# ESP32_Interface.net
KiCad netlist of a schematic drawn in Altium Designer
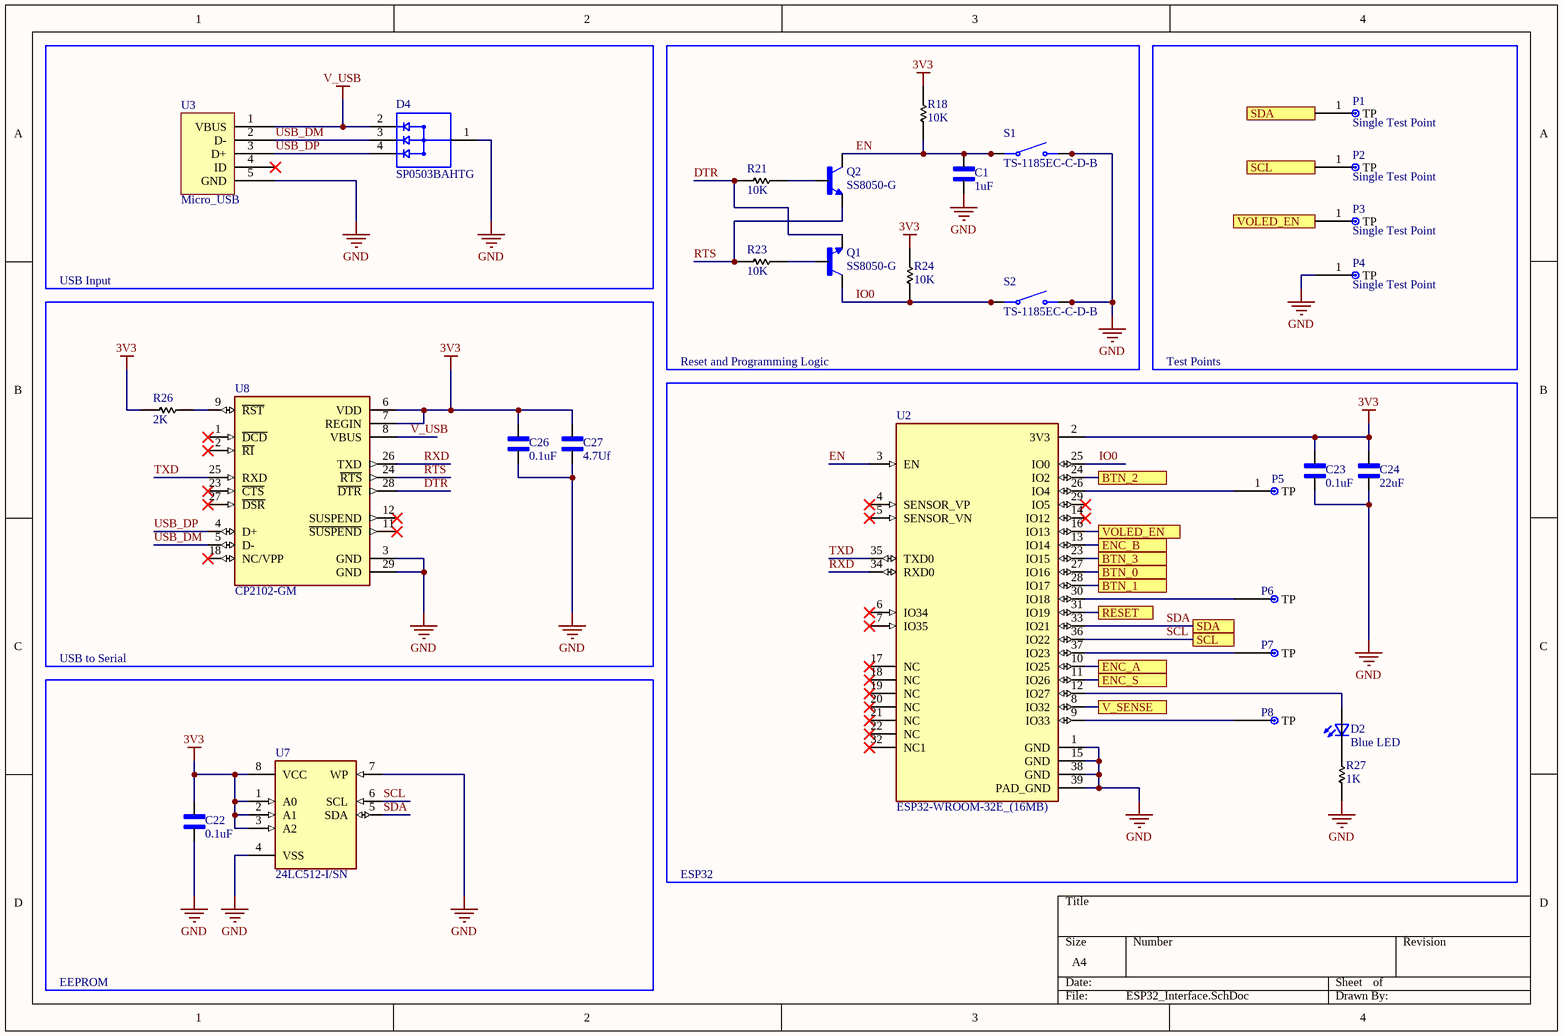
[diagram p0: ESP32_Interface.SchDoc]

(export (version "E")
  (design (tool "Eeschema 10.0.6"))
  (components
    (comp (ref "C1")
      (value "1uF")
      (footprint "CHIP_0603")
      (description "Generic 0603 Ceramic Capacitor")
      (fields (field (name "MP") "AC0402FR-071ML") (field (name "MF") "Yageo"))
      (libsource (lib "Guitar_Multi_Effect_lib") (part "0603 Ceramic Capacitor"))
    )
    (comp (ref "C22")
      (value "0.1uF")
      (footprint "CHIP_0603")
      (description "Generic 0603 Ceramic Capacitor")
      (fields (field (name "MP") "AC0402FR-071ML") (field (name "MF") "Yageo"))
      (libsource (lib "Guitar_Multi_Effect_lib") (part "0603 Ceramic Capacitor"))
    )
    (comp (ref "C23")
      (value "0.1uF")
      (footprint "CHIP_0603")
      (description "Generic 0603 Ceramic Capacitor")
      (fields (field (name "MP") "AC0402FR-071ML") (field (name "MF") "Yageo"))
      (libsource (lib "Guitar_Multi_Effect_lib") (part "0603 Ceramic Capacitor"))
    )
    (comp (ref "C24")
      (value "22uF")
      (footprint "CHIP_0603")
      (description "Generic 0603 Ceramic Capacitor")
      (fields (field (name "MP") "AC0402FR-071ML") (field (name "MF") "Yageo"))
      (libsource (lib "Guitar_Multi_Effect_lib") (part "0603 Ceramic Capacitor"))
    )
    (comp (ref "C26")
      (value "0.1uF")
      (footprint "CHIP_0603")
      (description "Generic 0603 Ceramic Capacitor")
      (fields (field (name "MP") "AC0402FR-071ML") (field (name "MF") "Yageo"))
      (libsource (lib "Guitar_Multi_Effect_lib") (part "0603 Ceramic Capacitor"))
    )
    (comp (ref "C27")
      (value "4.7Uf")
      (footprint "CHIP_0603")
      (description "Generic 0603 Ceramic Capacitor")
      (fields (field (name "MP") "AC0402FR-071ML") (field (name "MF") "Yageo"))
      (libsource (lib "Guitar_Multi_Effect_lib") (part "0603 Ceramic Capacitor"))
    )
    (comp (ref "D2")
      (value "Blue LED")
      (footprint "0603 LED Generic")
      (description "0603 Generic LED")
      (libsource (lib "Guitar_Multi_Effect_lib") (part "0603 Generic LED"))
    )
    (comp (ref "D4")
      (value "SP0503BAHTG")
      (footprint "Multi_Effect_Interface_lib:SP0503BAHTG")
      (description "8.5V Clamp Ipp Tvs Diode Surface Mount SOT-143-4")
      (fields (field (name "MF") "Littelfuse Inc.") (field (name "DIGI-KEY_PART_NUMBER") "F2715CT-ND"))
      (libsource (lib "Guitar_Multi_Effect_Interface_lib") (part "SP0503BAHTG"))
    )
    (comp (ref "P1")
      (value "Single Test Point")
      (footprint "1 Solder Pad")
      (libsource (lib "Guitar_Multi_Effect_Interface_lib") (part "Single Test Point"))
    )
    (comp (ref "P2")
      (value "Single Test Point")
      (footprint "1 Solder Pad")
      (libsource (lib "Guitar_Multi_Effect_Interface_lib") (part "Single Test Point"))
    )
    (comp (ref "P3")
      (value "Single Test Point")
      (footprint "1 Solder Pad")
      (libsource (lib "Guitar_Multi_Effect_Interface_lib") (part "Single Test Point"))
    )
    (comp (ref "P4")
      (value "Single Test Point")
      (footprint "1 Solder Pad")
      (libsource (lib "Guitar_Multi_Effect_Interface_lib") (part "Single Test Point"))
    )
    (comp (ref "P5")
      (value "Single Test Point")
      (footprint "1 Solder Pad")
      (libsource (lib "Guitar_Multi_Effect_Interface_lib") (part "Single Test Point"))
    )
    (comp (ref "P6")
      (value "Single Test Point")
      (footprint "1 Solder Pad")
      (libsource (lib "") (part "Single Test Point_1"))
    )
    (comp (ref "P7")
      (value "Single Test Point")
      (footprint "1 Solder Pad")
      (libsource (lib "") (part "Single Test Point_1"))
    )
    (comp (ref "P8")
      (value "Single Test Point")
      (footprint "1 Solder Pad")
      (libsource (lib "") (part "Single Test Point_1"))
    )
    (comp (ref "Q1")
      (value "SS8050-G")
      (footprint "SS8050-G")
      (description "NPN TRANSISTOR 1.5A 40V SOT-23 R")
      (libsource (lib "Guitar_Multi_Effect_lib") (part "SS8050-G"))
    )
    (comp (ref "Q2")
      (value "SS8050-G")
      (footprint "SS8050-G")
      (description "NPN TRANSISTOR 1.5A 40V SOT-23 R")
      (libsource (lib "") (part "SS8050-G_1"))
    )
    (comp (ref "R18")
      (value "10K")
      (footprint "CHIP_R_0603")
      (description "Generic 0603 Resistor")
      (libsource (lib "Guitar_Multi_Effect_lib") (part "0603 Generic Resistor"))
    )
    (comp (ref "R21")
      (value "10K")
      (footprint "CHIP_R_0603")
      (description "Generic 0603 Resistor")
      (libsource (lib "Guitar_Multi_Effect_lib") (part "0603 Generic Resistor"))
    )
    (comp (ref "R23")
      (value "10K")
      (footprint "CHIP_R_0603")
      (description "Generic 0603 Resistor")
      (libsource (lib "Guitar_Multi_Effect_lib") (part "0603 Generic Resistor"))
    )
    (comp (ref "R24")
      (value "10K")
      (footprint "CHIP_R_0603")
      (description "Generic 0603 Resistor")
      (libsource (lib "Guitar_Multi_Effect_lib") (part "0603 Generic Resistor"))
    )
    (comp (ref "R26")
      (value "2K")
      (footprint "CHIP_R_0603")
      (description "Generic 0603 Resistor")
      (libsource (lib "Guitar_Multi_Effect_lib") (part "0603 Generic Resistor"))
    )
    (comp (ref "R27")
      (value "1K")
      (footprint "CHIP_R_0603")
      (description "Generic 0603 Resistor")
      (libsource (lib "Guitar_Multi_Effect_lib") (part "0603 Generic Resistor"))
    )
    (comp (ref "S1")
      (value "TS-1185EC-C-D-B")
      (footprint "TS-1185EC-C-D-B")
      (description "SMD Tactile Switche - 3mm 2mm 50mA 3.65mm SPST 12V")
      (libsource (lib "Guitar_Multi_Effect_lib") (part "TS-1185EC-C-D-B"))
    )
    (comp (ref "S2")
      (value "TS-1185EC-C-D-B")
      (footprint "TS-1185EC-C-D-B")
      (description "SMD Tactile Switche - 3mm 2mm 50mA 3.65mm SPST 12V")
      (libsource (lib "Guitar_Multi_Effect_lib") (part "TS-1185EC-C-D-B"))
    )
    (comp (ref "U2")
      (value "ESP32-WROOM-32E_(16MB)")
      (footprint "MODULE_ESP32-WROOM-32E")
      (fields (field (name "MP") "ESP32-WROOM-32E (16MB)") (field (name "MF") "Espressif Systems"))
      (libsource (lib "Guitar_Multi_Effect_lib") (part "ESP32-WROOM-32E_(16MB)"))
    )
    (comp (ref "U3")
      (value "Micro_USB")
      (footprint "U254-051T-4BH83-F1S")
      (description "XKB Connectivity U254-051T-4BH83-F1S")
      (libsource (lib "Guitar_Multi_Effect_lib") (part "Micro_USB"))
    )
    (comp (ref "U7")
      (value "24LC512-I/SN")
      (footprint "24LC512-I/SN")
      (description "512K I2C Serial EEPROM")
      (libsource (lib "Guitar_Multi_Effect_lib") (part "24LC512-I/SN"))
    )
    (comp (ref "U8")
      (value "CP2102-GM")
      (footprint "QFN50P500X500X100-29N")
      (description "USB Bridge, USB to UART USB 2.0 UART Interface 28-QFN _5x5_")
      (fields (field (name "MF") "Silicon Labs"))
      (libsource (lib "Guitar_Multi_Effect_lib") (part "CP2102-GM"))
    )
  )
  (nets
    (net (code "1") (name "/BTN_0") (class "Default")
      (node (ref "U2") (pin "27") (pinfunction "IO16_27") (pintype "bidirectional"))
    )
    (net (code "2") (name "/BTN_1") (class "Default")
      (node (ref "U2") (pin "28") (pinfunction "IO17_28") (pintype "bidirectional"))
    )
    (net (code "3") (name "/BTN_2") (class "Default")
      (node (ref "U2") (pin "24") (pinfunction "IO2_24") (pintype "bidirectional"))
    )
    (net (code "4") (name "/BTN_3") (class "Default")
      (node (ref "U2") (pin "23") (pinfunction "IO15_23") (pintype "bidirectional"))
    )
    (net (code "5") (name "/DTR") (class "Default")
      (node (ref "Q1") (pin "2") (pinfunction "E_2") (pintype "passive"))
      (node (ref "R21") (pin "2") (pinfunction "2_2") (pintype "passive"))
      (node (ref "U8") (pin "28") (pinfunction "~{DTR}_28") (pintype "output"))
    )
    (net (code "6") (name "/EN") (class "Default")
      (node (ref "C1") (pin "1") (pinfunction "1_1") (pintype "passive"))
      (node (ref "Q2") (pin "3") (pinfunction "C_3") (pintype "passive"))
      (node (ref "R18") (pin "2") (pinfunction "2_2") (pintype "passive"))
      (node (ref "S1") (pin "1") (pinfunction "COM_1") (pintype "passive"))
      (node (ref "S1") (pin "2") (pinfunction "COM_2") (pintype "passive"))
      (node (ref "U2") (pin "3") (pinfunction "EN_3") (pintype "input"))
    )
    (net (code "7") (name "/ENC_A") (class "Default")
      (node (ref "U2") (pin "10") (pinfunction "IO25_10") (pintype "bidirectional"))
    )
    (net (code "8") (name "/ENC_B") (class "Default")
      (node (ref "U2") (pin "13") (pinfunction "IO14_13") (pintype "bidirectional"))
    )
    (net (code "9") (name "/ENC_S") (class "Default")
      (node (ref "U2") (pin "11") (pinfunction "IO26_11") (pintype "bidirectional"))
    )
    (net (code "10") (name "/IO0") (class "Default")
      (node (ref "Q1") (pin "3") (pinfunction "C_3") (pintype "passive"))
      (node (ref "R24") (pin "2") (pinfunction "2_2") (pintype "passive"))
      (node (ref "S2") (pin "1") (pinfunction "COM_1") (pintype "passive"))
      (node (ref "S2") (pin "2") (pinfunction "COM_2") (pintype "passive"))
      (node (ref "U2") (pin "25") (pinfunction "IO0_25") (pintype "bidirectional"))
    )
    (net (code "11") (name "/RESET") (class "Default")
      (node (ref "U2") (pin "31") (pinfunction "IO19_31") (pintype "bidirectional"))
    )
    (net (code "12") (name "/RTS") (class "Default")
      (node (ref "Q2") (pin "2") (pinfunction "E_2") (pintype "passive"))
      (node (ref "R23") (pin "2") (pinfunction "2_2") (pintype "passive"))
      (node (ref "U8") (pin "24") (pinfunction "~{RTS}_24") (pintype "output"))
    )
    (net (code "13") (name "/RXD") (class "Default")
      (node (ref "U2") (pin "34") (pinfunction "RXD0_34") (pintype "bidirectional"))
      (node (ref "U8") (pin "26") (pinfunction "TXD_26") (pintype "output"))
    )
    (net (code "14") (name "/SCL") (class "Default")
      (node (ref "P2") (pin "1") (pinfunction "TP_1") (pintype "passive"))
      (node (ref "U2") (pin "36") (pinfunction "IO22_36") (pintype "bidirectional"))
      (node (ref "U7") (pin "6") (pinfunction "SCL_6") (pintype "input"))
    )
    (net (code "15") (name "/SDA") (class "Default")
      (node (ref "P1") (pin "1") (pinfunction "TP_1") (pintype "passive"))
      (node (ref "U2") (pin "33") (pinfunction "IO21_33") (pintype "bidirectional"))
      (node (ref "U7") (pin "5") (pinfunction "SDA_5") (pintype "bidirectional"))
    )
    (net (code "16") (name "/TXD") (class "Default")
      (node (ref "U2") (pin "35") (pinfunction "TXD0_35") (pintype "bidirectional"))
      (node (ref "U8") (pin "25") (pinfunction "RXD_25") (pintype "input"))
    )
    (net (code "17") (name "/USB_DM") (class "Default")
      (node (ref "D4") (pin "3") (pinfunction "3_3") (pintype "passive"))
      (node (ref "U3") (pin "2") (pinfunction "D-_2") (pintype "passive"))
      (node (ref "U8") (pin "5") (pinfunction "D-_5") (pintype "bidirectional"))
    )
    (net (code "18") (name "/USB_DP") (class "Default")
      (node (ref "D4") (pin "4") (pinfunction "4_4") (pintype "passive"))
      (node (ref "U3") (pin "3") (pinfunction "D+_3") (pintype "passive"))
      (node (ref "U8") (pin "4") (pinfunction "D+_4") (pintype "bidirectional"))
    )
    (net (code "19") (name "/VOLED_EN") (class "Default")
      (node (ref "P3") (pin "1") (pinfunction "TP_1") (pintype "passive"))
      (node (ref "U2") (pin "16") (pinfunction "IO13_16") (pintype "bidirectional"))
    )
    (net (code "20") (name "/V_SENSE") (class "Default")
      (node (ref "U2") (pin "8") (pinfunction "IO32_8") (pintype "bidirectional"))
    )
    (net (code "21") (name "3V3") (class "Default")
      (node (ref "C22") (pin "1") (pinfunction "1_1") (pintype "passive"))
      (node (ref "C23") (pin "1") (pinfunction "1_1") (pintype "passive"))
      (node (ref "C24") (pin "1") (pinfunction "1_1") (pintype "passive"))
      (node (ref "C26") (pin "1") (pinfunction "1_1") (pintype "passive"))
      (node (ref "C27") (pin "1") (pinfunction "1_1") (pintype "passive"))
      (node (ref "R18") (pin "1") (pinfunction "1_1") (pintype "passive"))
      (node (ref "R24") (pin "1") (pinfunction "1_1") (pintype "passive"))
      (node (ref "R26") (pin "2") (pinfunction "2_2") (pintype "passive"))
      (node (ref "U2") (pin "2") (pinfunction "3V3_2") (pintype "power_in"))
      (node (ref "U7") (pin "1") (pinfunction "A0_1") (pintype "input"))
      (node (ref "U7") (pin "2") (pinfunction "A1_2") (pintype "input"))
      (node (ref "U7") (pin "3") (pinfunction "A2_3") (pintype "input"))
      (node (ref "U7") (pin "8") (pinfunction "VCC_8") (pintype "power_in"))
      (node (ref "U8") (pin "6") (pinfunction "VDD_6") (pintype "power_in"))
      (node (ref "U8") (pin "7") (pinfunction "REGIN_7") (pintype "power_in"))
    )
    (net (code "22") (name "GND") (class "Default")
      (node (ref "C1") (pin "2") (pinfunction "2_2") (pintype "passive"))
      (node (ref "C22") (pin "2") (pinfunction "2_2") (pintype "passive"))
      (node (ref "C23") (pin "2") (pinfunction "2_2") (pintype "passive"))
      (node (ref "C24") (pin "2") (pinfunction "2_2") (pintype "passive"))
      (node (ref "C26") (pin "2") (pinfunction "2_2") (pintype "passive"))
      (node (ref "C27") (pin "2") (pinfunction "2_2") (pintype "passive"))
      (node (ref "D4") (pin "1") (pinfunction "1_1") (pintype "passive"))
      (node (ref "P4") (pin "1") (pinfunction "TP_1") (pintype "passive"))
      (node (ref "R27") (pin "2") (pinfunction "2_2") (pintype "passive"))
      (node (ref "S1") (pin "3") (pinfunction "NO_3") (pintype "passive"))
      (node (ref "S1") (pin "4") (pinfunction "NO_4") (pintype "passive"))
      (node (ref "S2") (pin "3") (pinfunction "NO_3") (pintype "passive"))
      (node (ref "S2") (pin "4") (pinfunction "NO_4") (pintype "passive"))
      (node (ref "U2") (pin "1") (pinfunction "GND_1") (pintype "power_in"))
      (node (ref "U2") (pin "15") (pinfunction "GND_15") (pintype "power_in"))
      (node (ref "U2") (pin "38") (pinfunction "GND_38") (pintype "power_in"))
      (node (ref "U2") (pin "39") (pinfunction "PAD_GND_39") (pintype "power_in"))
      (node (ref "U3") (pin "5") (pinfunction "GND_5") (pintype "passive"))
      (node (ref "U7") (pin "4") (pinfunction "VSS_4") (pintype "passive"))
      (node (ref "U7") (pin "7") (pinfunction "WP_7") (pintype "input"))
      (node (ref "U8") (pin "29") (pinfunction "GND_29") (pintype "power_in"))
      (node (ref "U8") (pin "3") (pinfunction "GND_3") (pintype "power_in"))
    )
    (net (code "23") (name "Net-(D2-A2)") (class "Default")
      (node (ref "D2") (pin "2") (pinfunction "A2_2") (pintype "passive"))
      (node (ref "U2") (pin "12") (pinfunction "IO27_12") (pintype "bidirectional"))
    )
    (net (code "24") (name "Net-(D2-K2)") (class "Default")
      (node (ref "D2") (pin "1") (pinfunction "K2_1") (pintype "passive"))
      (node (ref "R27") (pin "1") (pinfunction "1_1") (pintype "passive"))
    )
    (net (code "25") (name "Net-(P5-TP)") (class "Default")
      (node (ref "P5") (pin "1") (pinfunction "TP_1") (pintype "passive"))
      (node (ref "U2") (pin "26") (pinfunction "IO4_26") (pintype "bidirectional"))
    )
    (net (code "26") (name "Net-(P6-TP)") (class "Default")
      (node (ref "P6") (pin "1") (pinfunction "TP_1") (pintype "passive"))
      (node (ref "U2") (pin "30") (pinfunction "IO18_30") (pintype "bidirectional"))
    )
    (net (code "27") (name "Net-(P7-TP)") (class "Default")
      (node (ref "P7") (pin "1") (pinfunction "TP_1") (pintype "passive"))
      (node (ref "U2") (pin "37") (pinfunction "IO23_37") (pintype "bidirectional"))
    )
    (net (code "28") (name "Net-(P8-TP)") (class "Default")
      (node (ref "P8") (pin "1") (pinfunction "TP_1") (pintype "passive"))
      (node (ref "U2") (pin "9") (pinfunction "IO33_9") (pintype "bidirectional"))
    )
    (net (code "29") (name "Net-(Q1-B)") (class "Default")
      (node (ref "Q1") (pin "1") (pinfunction "B_1") (pintype "passive"))
      (node (ref "R23") (pin "1") (pinfunction "1_1") (pintype "passive"))
    )
    (net (code "30") (name "Net-(Q2-B)") (class "Default")
      (node (ref "Q2") (pin "1") (pinfunction "B_1") (pintype "passive"))
      (node (ref "R21") (pin "1") (pinfunction "1_1") (pintype "passive"))
    )
    (net (code "31") (name "Net-(U8-~{RST})") (class "Default")
      (node (ref "R26") (pin "1") (pinfunction "1_1") (pintype "passive"))
      (node (ref "U8") (pin "9") (pinfunction "~{RST}_9") (pintype "bidirectional"))
    )
    (net (code "32") (name "V_USB") (class "Default")
      (node (ref "D4") (pin "2") (pinfunction "2_2") (pintype "passive"))
      (node (ref "U3") (pin "1") (pinfunction "VBUS_1") (pintype "passive"))
      (node (ref "U8") (pin "8") (pinfunction "VBUS_8") (pintype "power_in"))
    )
    (net (code "33") (name "unconnected-(U2-IO5-Pad29)") (class "Default")
      (node (ref "U2") (pin "29") (pinfunction "IO5_29") (pintype "bidirectional+no_connect"))
    )
    (net (code "34") (name "unconnected-(U2-IO12-Pad14)") (class "Default")
      (node (ref "U2") (pin "14") (pinfunction "IO12_14") (pintype "bidirectional+no_connect"))
    )
    (net (code "35") (name "unconnected-(U2-IO34-Pad6)") (class "Default")
      (node (ref "U2") (pin "6") (pinfunction "IO34_6") (pintype "input+no_connect"))
    )
    (net (code "36") (name "unconnected-(U2-IO35-Pad7)") (class "Default")
      (node (ref "U2") (pin "7") (pinfunction "IO35_7") (pintype "input+no_connect"))
    )
    (net (code "37") (name "unconnected-(U2-NC-Pad17)") (class "Default")
      (node (ref "U2") (pin "17") (pinfunction "NC_17") (pintype "passive+no_connect"))
    )
    (net (code "38") (name "unconnected-(U2-NC-Pad18)") (class "Default")
      (node (ref "U2") (pin "18") (pinfunction "NC_18") (pintype "passive+no_connect"))
    )
    (net (code "39") (name "unconnected-(U2-NC-Pad19)") (class "Default")
      (node (ref "U2") (pin "19") (pinfunction "NC_19") (pintype "passive+no_connect"))
    )
    (net (code "40") (name "unconnected-(U2-NC-Pad20)") (class "Default")
      (node (ref "U2") (pin "20") (pinfunction "NC_20") (pintype "passive+no_connect"))
    )
    (net (code "41") (name "unconnected-(U2-NC-Pad21)") (class "Default")
      (node (ref "U2") (pin "21") (pinfunction "NC_21") (pintype "passive+no_connect"))
    )
    (net (code "42") (name "unconnected-(U2-NC-Pad22)") (class "Default")
      (node (ref "U2") (pin "22") (pinfunction "NC_22") (pintype "passive+no_connect"))
    )
    (net (code "43") (name "unconnected-(U2-NC1-Pad32)") (class "Default")
      (node (ref "U2") (pin "32") (pinfunction "NC1_32") (pintype "passive+no_connect"))
    )
    (net (code "44") (name "unconnected-(U2-SENSOR_VN-Pad5)") (class "Default")
      (node (ref "U2") (pin "5") (pinfunction "SENSOR_VN_5") (pintype "input+no_connect"))
    )
    (net (code "45") (name "unconnected-(U2-SENSOR_VP-Pad4)") (class "Default")
      (node (ref "U2") (pin "4") (pinfunction "SENSOR_VP_4") (pintype "input+no_connect"))
    )
    (net (code "46") (name "unconnected-(U3-ID-Pad4)") (class "Default")
      (node (ref "U3") (pin "4") (pinfunction "ID_4") (pintype "passive+no_connect"))
    )
    (net (code "47") (name "unconnected-(U8-NC{slash}VPP-Pad18)") (class "Default")
      (node (ref "U8") (pin "18") (pinfunction "NC/VPP_18") (pintype "bidirectional+no_connect"))
    )
    (net (code "48") (name "unconnected-(U8-SUSPEND-Pad12)") (class "Default")
      (node (ref "U8") (pin "12") (pinfunction "SUSPEND_12") (pintype "output+no_connect"))
    )
    (net (code "49") (name "unconnected-(U8-~{CTS}-Pad23)") (class "Default")
      (node (ref "U8") (pin "23") (pinfunction "~{CTS}_23") (pintype "input+no_connect"))
    )
    (net (code "50") (name "unconnected-(U8-~{DCD}-Pad1)") (class "Default")
      (node (ref "U8") (pin "1") (pinfunction "~{DCD}_1") (pintype "input+no_connect"))
    )
    (net (code "51") (name "unconnected-(U8-~{DSR}-Pad27)") (class "Default")
      (node (ref "U8") (pin "27") (pinfunction "~{DSR}_27") (pintype "input+no_connect"))
    )
    (net (code "52") (name "unconnected-(U8-~{RI}-Pad2)") (class "Default")
      (node (ref "U8") (pin "2") (pinfunction "~{RI}_2") (pintype "input+no_connect"))
    )
    (net (code "53") (name "unconnected-(U8-~{SUSPEND}-Pad11)") (class "Default")
      (node (ref "U8") (pin "11") (pinfunction "~{SUSPEND}_11") (pintype "output+no_connect"))
    )
  )
)
